# LED_Point.net
KiCad netlist of a schematic drawn in Altium Designer
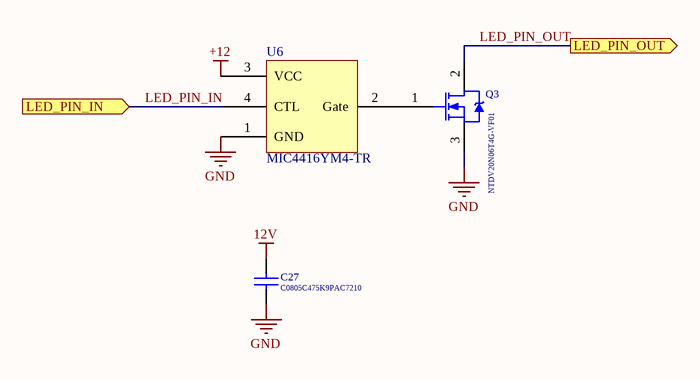
[diagram p0: LED_Point.SchDoc]

(export (version "E")
  (design (tool "Eeschema 10.0.6"))
  (components
    (comp (ref "C27")
      (value "C0805C475K9PAC7210")
      (footprint "CAP SMD 0805")
      (description "4.7 µF ±10% 6.3V Ceramic Capacitor X5R 0805 (2012 Metric)")
      (fields (field (name "PUBLISHER") "Altium Limited"))
      (libsource (lib "DIY-USB Led Controller") (part "Cap_3_1"))
    )
    (comp (ref "Q3")
      (value "NTDV20N06T4G-VF01")
      (footprint "DPAK228P991X238-3N")
      (description "MOSFET N-CH 60V 20A DPAK")
      (fields
        (field (name "MANUFACTURE PART NUMBER") "IRF540N_R4942")
        (field (name "PUBLISHER") "Altium Limited")
      )
      (libsource (lib "HYD_EMER_2") (part "IRF540NS"))
    )
    (comp (ref "U6")
      (value "MIC4416YM4-TR")
      (footprint "MICROCHIP SOT-143-4")
      (description "IC GATE DRVR LOW-SIDE SOT143")
      (fields (field (name "MANUFACTURER") "Microchip Technology"))
      (libsource (lib "Celestial Altium Library - altium_library") (part "MICROCHIP MIC4416"))
    )
  )
  (nets
    (net (code "1") (name "+12") (class "Default")
      (node (ref "U6") (pin "3") (pinfunction "VCC_3") (pintype "passive"))
    )
    (net (code "2") (name "/LED_PIN_IN") (class "Default")
      (node (ref "U6") (pin "4") (pinfunction "CTL_4") (pintype "passive"))
    )
    (net (code "3") (name "/LED_PIN_OUT") (class "Default")
      (node (ref "Q3") (pin "2") (pinfunction "D_2") (pintype "passive"))
    )
    (net (code "4") (name "12V") (class "Default")
      (node (ref "C27") (pin "2") (pinfunction "2_2") (pintype "passive"))
    )
    (net (code "5") (name "GND") (class "Default")
      (node (ref "C27") (pin "1") (pinfunction "1_1") (pintype "passive"))
      (node (ref "Q3") (pin "3") (pinfunction "S_3") (pintype "passive"))
      (node (ref "U6") (pin "1") (pinfunction "GND_1") (pintype "passive"))
    )
    (net (code "6") (name "Net-(Q3-G)") (class "Default")
      (node (ref "Q3") (pin "1") (pinfunction "G_1") (pintype "passive"))
      (node (ref "U6") (pin "2") (pinfunction "Gate_2") (pintype "passive"))
    )
  )
)
